# ST_LINK_V2-1.net
KiCad netlist of a schematic drawn in Altium Designer
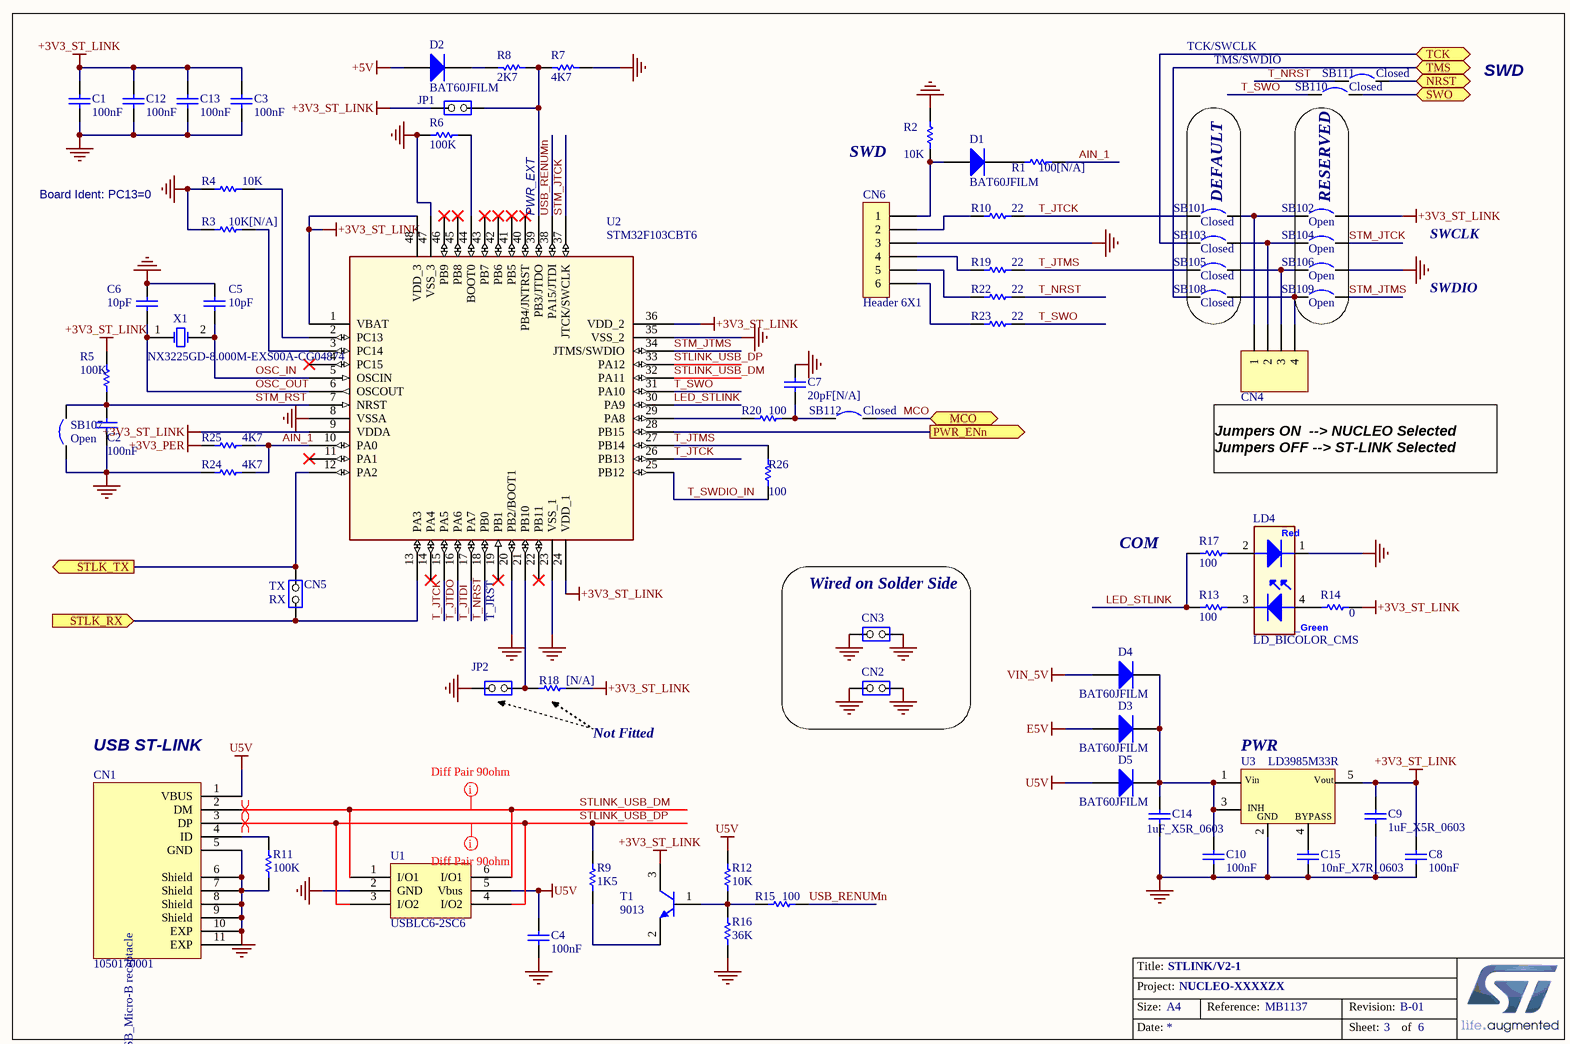
[diagram p0: ST_LINK_V2-1.SCHDOC]

(export (version "E")
  (design (tool "Eeschema 10.0.6"))
  (components
    (comp (ref "C1")
      (value "100nF")
      (footprint "0603C")
      (description "Capacitor 0402 / 0603 / 0805")
      (libsource (lib "MCD_TOOLS") (part "Capacitor_ST"))
    )
    (comp (ref "C2")
      (value "100nF")
      (footprint "0603C")
      (description "Capacitor 0402 / 0603 / 0805")
      (libsource (lib "MCD_TOOLS") (part "Capacitor_ST"))
    )
    (comp (ref "C3")
      (value "100nF")
      (footprint "0603C")
      (description "Capacitor 0402 / 0603 / 0805")
      (libsource (lib "MCD_TOOLS") (part "Capacitor_ST"))
    )
    (comp (ref "C4")
      (value "100nF")
      (footprint "0603C")
      (description "Capacitor 0402 / 0603 / 0805")
      (libsource (lib "MCD_TOOLS") (part "Capacitor_ST"))
    )
    (comp (ref "C5")
      (value "10pF")
      (footprint "0603C")
      (description "Capacitor 0402 / 0603 / 0805")
      (libsource (lib "MCD_TOOLS") (part "Capacitor_ST"))
    )
    (comp (ref "C6")
      (value "10pF")
      (footprint "0603C")
      (description "Capacitor 0402 / 0603 / 0805")
      (libsource (lib "MCD_TOOLS") (part "Capacitor_ST"))
    )
    (comp (ref "C7")
      (value "20pF[N/A]")
      (footprint "0603C")
      (description "Capacitor 0402 / 0603 / 0805")
      (libsource (lib "MCD_TOOLS") (part "Capacitor_ST"))
    )
    (comp (ref "C8")
      (value "100nF")
      (footprint "0603C")
      (description "Capacitor 0402 / 0603 / 0805")
      (libsource (lib "MCD_TOOLS") (part "Capacitor_ST"))
    )
    (comp (ref "C9")
      (value "1uF_X5R_0603")
      (footprint "0603C")
      (description "0603  X5R 1µF")
      (fields (field (name "TOLERANCE") "10%"))
      (libsource (lib "MB963_1") (part "CAP SMD 0603  X5R 1µF 25V 10%"))
    )
    (comp (ref "C10")
      (value "100nF")
      (footprint "0603C")
      (description "Capacitor 0402 / 0603 / 0805")
      (libsource (lib "MCD_TOOLS") (part "Capacitor_ST"))
    )
    (comp (ref "C12")
      (value "100nF")
      (footprint "0603C")
      (description "Capacitor 0402 / 0603 / 0805")
      (libsource (lib "MCD_TOOLS") (part "Capacitor_ST"))
    )
    (comp (ref "C13")
      (value "100nF")
      (footprint "0603C")
      (description "Capacitor 0402 / 0603 / 0805")
      (libsource (lib "MCD_TOOLS") (part "Capacitor_ST"))
    )
    (comp (ref "C14")
      (value "1uF_X5R_0603")
      (footprint "0603C")
      (description "0603  X5R 1µF")
      (fields (field (name "TOLERANCE") "10%"))
      (libsource (lib "MB963_1") (part "CAP SMD 0603  X5R 1µF 25V 10%"))
    )
    (comp (ref "C15")
      (value "10nF_X7R_0603")
      (footprint "0603C")
      (description "0603  X7R 10NF")
      (fields (field (name "TOLERANCE") "10%"))
      (libsource (lib "MB963_1") (part "CAP SMD 0603  X7R 10000PF 50V 10%"))
    )
    (comp (ref "CN1")
      (value "1050170001")
      (footprint "Molex_1050170001")
      (libsource (lib "Smartphone_accessory") (part "1050170001"))
    )
    (comp (ref "CN2") (value "~") (footprint "HDR_1x2_2R54_V_M") (libsource (lib "*") (part "JP2")))
    (comp (ref "CN3") (value "~") (footprint "HDR_1x2_2R54_V_M") (libsource (lib "*") (part "JP2")))
    (comp (ref "CN4")
      (value "Header 4")
      (footprint "HDR_1x4_2R54_V_M")
      (description "Header, 4-Pin, Single row")
      (fields (field (name "PUBLISHER") "Altium Limited"))
      (libsource (lib "Nucleo_64") (part "Header 4"))
    )
    (comp (ref "CN5") (value "~") (footprint "HDR_1x2_2R54_V_M_S") (libsource (lib "MCD_TOOLS") (part "JP2")))
    (comp (ref "CN6")
      (value "Header 6X1")
      (footprint "HDR_1x6_2R54_V_M")
      (description "Header, 6-Pin, Single row")
      (fields (field (name "PUBLISHER") "Altium Limited"))
      (libsource (lib "Nucleo_64") (part "Header 6X1"))
    )
    (comp (ref "D1")
      (value "BAT60JFILM")
      (footprint "SOD-323")
      (libsource (lib "MB1137") (part "BAT60JFILM"))
    )
    (comp (ref "D2")
      (value "BAT60JFILM")
      (footprint "SOD-323")
      (description "Default Diode")
      (fields (field (name "PUBLISHER") "Altium Limited"))
      (libsource (lib "MB1144_1") (part "Diode"))
    )
    (comp (ref "D3")
      (value "BAT60JFILM")
      (footprint "SOD-323")
      (libsource (lib "MB1137") (part "BAT60JFILM"))
    )
    (comp (ref "D4")
      (value "BAT60JFILM")
      (footprint "SOD-323")
      (libsource (lib "MB1137") (part "BAT60JFILM"))
    )
    (comp (ref "D5")
      (value "BAT60JFILM")
      (footprint "SOD-323")
      (libsource (lib "MB1137") (part "BAT60JFILM"))
    )
    (comp (ref "JP1") (value "~") (footprint "HDR_1x2_2R54_V_M_S") (libsource (lib "*") (part "JP2")))
    (comp (ref "JP2") (value "~") (footprint "HDR_1x2_2R54_V_M_S") (libsource (lib "*") (part "JP2")))
    (comp (ref "LD4")
      (value "LD_BICOLOR_CMS")
      (footprint "HSMF-A201")
      (description "Bicolor Led")
      (libsource (lib "MB1137") (part "LD_BICOLOR_CMS"))
    )
    (comp (ref "R1")
      (value "100[N/A]")
      (footprint "0603R")
      (description "Resistor 0402 or 0603 or 0805")
      (libsource (lib "") (part "Res1_1"))
    )
    (comp (ref "R2")
      (value "10K")
      (footprint "0603R")
      (description "Resistor 0402 or 0603 or 0805")
      (libsource (lib "") (part "Res1_1"))
    )
    (comp (ref "R3")
      (value "10K[N/A]")
      (footprint "0603R")
      (description "Resistor 0402 or 0603 or 0805")
      (libsource (lib "") (part "Res1_1"))
    )
    (comp (ref "R4")
      (value "10K")
      (footprint "0603R")
      (description "Resistor 0402 or 0603 or 0805")
      (libsource (lib "") (part "Res1_1"))
    )
    (comp (ref "R5")
      (value "100K")
      (footprint "0603R")
      (description "Resistor 0402 or 0603 or 0805")
      (libsource (lib "") (part "Res1_1"))
    )
    (comp (ref "R6")
      (value "100K")
      (footprint "0603R")
      (description "Resistor 0402 or 0603 or 0805")
      (libsource (lib "") (part "Res1_1"))
    )
    (comp (ref "R7")
      (value "4K7")
      (footprint "0603R")
      (description "Resistor")
      (fields (field (name "PUBLISHER") "Altium Limited"))
      (libsource (lib "") (part "Res1_2"))
    )
    (comp (ref "R8")
      (value "2K7")
      (footprint "0603R")
      (description "Resistor")
      (fields (field (name "PUBLISHER") "Altium Limited"))
      (libsource (lib "") (part "Res1_2"))
    )
    (comp (ref "R9")
      (value "1K5")
      (footprint "0603R")
      (description "Resistor 0402 or 0603 or 0805")
      (libsource (lib "") (part "Res1_1"))
    )
    (comp (ref "R10")
      (value "22")
      (footprint "0603R")
      (description "Resistor 0402 or 0603 or 0805")
      (libsource (lib "") (part "Res1_1"))
    )
    (comp (ref "R11")
      (value "100K")
      (footprint "0603R")
      (description "Resistor 0402 or 0603 or 0805")
      (libsource (lib "") (part "Res1_1"))
    )
    (comp (ref "R12")
      (value "10K")
      (footprint "0603R")
      (description "Resistor")
      (fields (field (name "PUBLISHER") "Altium Limited"))
      (libsource (lib "Miscellaneous Devices") (part "Res1"))
    )
    (comp (ref "R13")
      (value "100")
      (footprint "0603R")
      (description "Resistor 0402 or 0603 or 0805")
      (libsource (lib "") (part "Res1_1"))
    )
    (comp (ref "R14")
      (value "0")
      (footprint "0603R")
      (description "Resistor 0402 or 0603 or 0805")
      (libsource (lib "") (part "Res1_1"))
    )
    (comp (ref "R15")
      (value "100")
      (footprint "0603R")
      (description "Resistor 0402 or 0603 or 0805")
      (libsource (lib "") (part "Res1_1"))
    )
    (comp (ref "R16")
      (value "36K")
      (footprint "0603R")
      (description "Resistor")
      (fields (field (name "PUBLISHER") "Altium Limited"))
      (libsource (lib "Miscellaneous Devices") (part "Res1"))
    )
    (comp (ref "R17")
      (value "100")
      (footprint "0603R")
      (description "Resistor 0402 or 0603 or 0805")
      (libsource (lib "") (part "Res1_1"))
    )
    (comp (ref "R18")
      (value "[N/A]")
      (footprint "0603R")
      (description "Resistor")
      (fields (field (name "PUBLISHER") "Altium Limited"))
      (libsource (lib "Miscellaneous Devices") (part "Res1"))
    )
    (comp (ref "R19")
      (value "22")
      (footprint "0603R")
      (description "Resistor 0402 or 0603 or 0805")
      (libsource (lib "") (part "Res1_1"))
    )
    (comp (ref "R20")
      (value "100")
      (footprint "0603R")
      (description "Resistor 0402 or 0603 or 0805")
      (libsource (lib "") (part "Res1_1"))
    )
    (comp (ref "R22")
      (value "22")
      (footprint "0603R")
      (description "Resistor 0402 or 0603 or 0805")
      (libsource (lib "") (part "Res1_1"))
    )
    (comp (ref "R23")
      (value "22")
      (footprint "0603R")
      (description "Resistor 0402 or 0603 or 0805")
      (libsource (lib "") (part "Res1_1"))
    )
    (comp (ref "R24")
      (value "4K7")
      (footprint "0603R")
      (description "Resistor 0402 or 0603 or 0805")
      (libsource (lib "") (part "Res1_1"))
    )
    (comp (ref "R25")
      (value "4K7")
      (footprint "0603R")
      (description "Resistor 0402 or 0603 or 0805")
      (libsource (lib "") (part "Res1_1"))
    )
    (comp (ref "R26")
      (value "100")
      (footprint "0603R")
      (description "Resistor 0402 or 0603 or 0805")
      (libsource (lib "") (part "Res1_1"))
    )
    (comp (ref "SB101")
      (value "Closed")
      (footprint "SB_0603")
      (description "Circuit Breaker")
      (fields (field (name "PUBLISHER") "Altium Limited"))
      (libsource (lib "MB1167") (part "Circuit Breaker_close"))
    )
    (comp (ref "SB102")
      (value "Open")
      (footprint "SB_0603")
      (description "Circuit Breaker")
      (fields (field (name "PUBLISHER") "Altium Limited"))
      (libsource (lib "MB1167") (part "Circuit Breaker"))
    )
    (comp (ref "SB103")
      (value "Closed")
      (footprint "SB_0603")
      (description "Circuit Breaker")
      (fields (field (name "PUBLISHER") "Altium Limited"))
      (libsource (lib "MB1167") (part "Circuit Breaker_close"))
    )
    (comp (ref "SB104")
      (value "Open")
      (footprint "SB_0603")
      (description "Circuit Breaker")
      (fields (field (name "PUBLISHER") "Altium Limited"))
      (libsource (lib "MB1167") (part "Circuit Breaker"))
    )
    (comp (ref "SB105")
      (value "Closed")
      (footprint "SB_0603")
      (description "Circuit Breaker")
      (fields (field (name "PUBLISHER") "Altium Limited"))
      (libsource (lib "MB1167") (part "Circuit Breaker_close"))
    )
    (comp (ref "SB106")
      (value "Open")
      (footprint "SB_0603")
      (description "Circuit Breaker")
      (fields (field (name "PUBLISHER") "Altium Limited"))
      (libsource (lib "MB1167") (part "Circuit Breaker"))
    )
    (comp (ref "SB107")
      (value "Open")
      (footprint "SB_0603")
      (description "Circuit Breaker")
      (fields (field (name "PUBLISHER") "Altium Limited"))
      (libsource (lib "MB1167") (part "Circuit Breaker"))
    )
    (comp (ref "SB108")
      (value "Closed")
      (footprint "SB_0603")
      (description "Circuit Breaker")
      (fields (field (name "PUBLISHER") "Altium Limited"))
      (libsource (lib "MB1167") (part "Circuit Breaker_close"))
    )
    (comp (ref "SB109")
      (value "Open")
      (footprint "SB_0603")
      (description "Circuit Breaker")
      (fields (field (name "PUBLISHER") "Altium Limited"))
      (libsource (lib "MB1167") (part "Circuit Breaker"))
    )
    (comp (ref "SB110")
      (value "Closed")
      (footprint "SB_0603")
      (description "Circuit Breaker")
      (fields (field (name "PUBLISHER") "Altium Limited"))
      (libsource (lib "MB1167") (part "Circuit Breaker_close"))
    )
    (comp (ref "SB111")
      (value "Closed")
      (footprint "SB_0603")
      (description "Circuit Breaker")
      (fields (field (name "PUBLISHER") "Altium Limited"))
      (libsource (lib "MB1167") (part "Circuit Breaker_close"))
    )
    (comp (ref "SB112")
      (value "Closed")
      (footprint "SB_0603")
      (description "Circuit Breaker")
      (fields (field (name "PUBLISHER") "Altium Limited"))
      (libsource (lib "MB1167") (part "Circuit Breaker_close"))
    )
    (comp (ref "T1")
      (value "9013")
      (footprint "SOT-23")
      (description "NPN Bipolar Transistor")
      (fields (field (name "PUBLISHER") "Altium Limited"))
      (libsource (lib "MB1167") (part "NPN"))
    )
    (comp (ref "U1")
      (value "USBLC6-2SC6")
      (footprint "SOT23-6L")
      (libsource (lib "MB1137") (part "USBLC6-2SC6"))
    )
    (comp (ref "U2")
      (value "STM32F103CBT6")
      (footprint "LQFP48_0R5_7x7")
      (description "Medium-density performance line ARM-based 32-bit MCU with 64KB Flash")
      (libsource (lib "Nucleo_64") (part "STM32F103CBT6"))
    )
    (comp (ref "U3")
      (value "LD3985M33R")
      (footprint "SOT-23-5L")
      (description "Ultra low drop-low noise BiCMOS voltage, regulators low ESR capacitors compatible")
      (libsource (lib "MCD_TOOLS") (part "LD3985M33R"))
    )
    (comp (ref "X1")
      (value "NX3225GD-8.000M-EXS00A-CG04874")
      (footprint "OSC_2SM_3R2x2R5")
      (description "Crystal Oscillator")
      (fields (field (name "PUBLISHER") "Altium Limited"))
      (libsource (lib "MB963_1") (part "XTAL"))
    )
  )
  (nets
    (net (code "1") (name "+3V3_PER") (class "Default")
      (node (ref "R25") (pin "1") (pinfunction "1_1") (pintype "passive"))
    )
    (net (code "2") (name "+3V3_ST_LINK") (class "Default")
      (node (ref "C1") (pin "2") (pinfunction "2_2") (pintype "passive"))
      (node (ref "C12") (pin "2") (pinfunction "2_2") (pintype "passive"))
      (node (ref "C13") (pin "2") (pinfunction "2_2") (pintype "passive"))
      (node (ref "C3") (pin "2") (pinfunction "2_2") (pintype "passive"))
      (node (ref "C8") (pin "2") (pinfunction "2_2") (pintype "passive"))
      (node (ref "C9") (pin "1") (pinfunction "1_1") (pintype "passive"))
      (node (ref "JP1") (pin "1") (pinfunction "COMMON_1") (pintype "passive"))
      (node (ref "R14") (pin "2") (pinfunction "2_2") (pintype "passive"))
      (node (ref "R18") (pin "1") (pinfunction "1_1") (pintype "passive"))
      (node (ref "R5") (pin "2") (pinfunction "2_2") (pintype "passive"))
      (node (ref "SB102") (pin "2") (pinfunction "2_2") (pintype "passive"))
      (node (ref "T1") (pin "3") (pinfunction "C_3") (pintype "passive"))
      (node (ref "U2") (pin "1") (pinfunction "VBAT_1") (pintype "power_in"))
      (node (ref "U2") (pin "24") (pinfunction "VDD_1_24") (pintype "power_in"))
      (node (ref "U2") (pin "36") (pinfunction "VDD_2_36") (pintype "power_in"))
      (node (ref "U2") (pin "48") (pinfunction "VDD_3_48") (pintype "power_in"))
      (node (ref "U2") (pin "9") (pinfunction "VDDA_9") (pintype "power_in"))
      (node (ref "U3") (pin "5") (pinfunction "Vout_5") (pintype "passive"))
    )
    (net (code "3") (name "+5V") (class "Default")
      (node (ref "D2") (pin "1") (pinfunction "A_1") (pintype "passive"))
    )
    (net (code "4") (name "/AIN_1") (class "Default")
      (node (ref "R1") (pin "2") (pinfunction "2_2") (pintype "passive"))
      (node (ref "R24") (pin "2") (pinfunction "2_2") (pintype "passive"))
      (node (ref "R25") (pin "2") (pinfunction "2_2") (pintype "passive"))
      (node (ref "U2") (pin "10") (pinfunction "PA0_10") (pintype "bidirectional"))
    )
    (net (code "5") (name "/LED_STLINK") (class "Default")
      (node (ref "R13") (pin "1") (pinfunction "1_1") (pintype "passive"))
      (node (ref "R17") (pin "1") (pinfunction "1_1") (pintype "passive"))
      (node (ref "U2") (pin "30") (pinfunction "PA9_30") (pintype "bidirectional"))
    )
    (net (code "6") (name "/MCO") (class "Default")
      (node (ref "SB112") (pin "2") (pinfunction "2_2") (pintype "passive"))
    )
    (net (code "7") (name "/NRST") (class "Default")
      (node (ref "SB111") (pin "2") (pinfunction "2_2") (pintype "passive"))
    )
    (net (code "8") (name "/OSC_IN") (class "Default")
      (node (ref "C5") (pin "1") (pinfunction "1_1") (pintype "passive"))
      (node (ref "U2") (pin "5") (pinfunction "OSCIN_5") (pintype "input"))
      (node (ref "X1") (pin "2") (pinfunction "OSC2_2") (pintype "passive"))
    )
    (net (code "9") (name "/OSC_OUT") (class "Default")
      (node (ref "C6") (pin "1") (pinfunction "1_1") (pintype "passive"))
      (node (ref "U2") (pin "6") (pinfunction "OSCOUT_6") (pintype "output"))
      (node (ref "X1") (pin "1") (pinfunction "OSC1_1") (pintype "passive"))
    )
    (net (code "10") (name "/PWR_ENn") (class "Default")
      (node (ref "U2") (pin "28") (pinfunction "PB15_28") (pintype "bidirectional"))
    )
    (net (code "11") (name "/STLINK_USB_DM") (class "Default")
      (node (ref "CN1") (pin "2") (pinfunction "DM_2") (pintype "passive"))
      (node (ref "U1") (pin "1") (pinfunction "I/O1_1") (pintype "passive"))
      (node (ref "U1") (pin "6") (pinfunction "I/O1_6") (pintype "passive"))
      (node (ref "U2") (pin "32") (pinfunction "PA11_32") (pintype "bidirectional"))
    )
    (net (code "12") (name "/STLINK_USB_DP") (class "Default")
      (node (ref "CN1") (pin "3") (pinfunction "DP_3") (pintype "passive"))
      (node (ref "R9") (pin "1") (pinfunction "1_1") (pintype "passive"))
      (node (ref "U1") (pin "3") (pinfunction "I/O2_3") (pintype "passive"))
      (node (ref "U1") (pin "4") (pinfunction "I/O2_4") (pintype "passive"))
      (node (ref "U2") (pin "33") (pinfunction "PA12_33") (pintype "bidirectional"))
    )
    (net (code "13") (name "/STLK_RX") (class "Default")
      (node (ref "CN5") (pin "1") (pinfunction "COMMON_1") (pintype "passive"))
      (node (ref "U2") (pin "13") (pinfunction "PA3_13") (pintype "bidirectional"))
    )
    (net (code "14") (name "/STLK_TX") (class "Default")
      (node (ref "CN5") (pin "2") (pinfunction "NO_2") (pintype "passive"))
      (node (ref "U2") (pin "12") (pinfunction "PA2_12") (pintype "bidirectional"))
    )
    (net (code "15") (name "/STM_JTCK") (class "Default")
      (node (ref "SB104") (pin "2") (pinfunction "2_2") (pintype "passive"))
      (node (ref "U2") (pin "37") (pinfunction "JTCK/SWCLK_37") (pintype "bidirectional"))
    )
    (net (code "16") (name "/STM_JTMS") (class "Default")
      (node (ref "SB109") (pin "2") (pinfunction "2_2") (pintype "passive"))
      (node (ref "U2") (pin "34") (pinfunction "JTMS/SWDIO_34") (pintype "bidirectional"))
    )
    (net (code "17") (name "/STM_RST") (class "Default")
      (node (ref "C2") (pin "2") (pinfunction "2_2") (pintype "passive"))
      (node (ref "R5") (pin "1") (pinfunction "1_1") (pintype "passive"))
      (node (ref "SB107") (pin "2") (pinfunction "2_2") (pintype "passive"))
      (node (ref "U2") (pin "7") (pinfunction "NRST_7") (pintype "input"))
    )
    (net (code "18") (name "/SWO") (class "Default")
      (node (ref "SB110") (pin "2") (pinfunction "2_2") (pintype "passive"))
    )
    (net (code "19") (name "/TCK") (class "Default")
      (node (ref "SB103") (pin "1") (pinfunction "1_1") (pintype "passive"))
    )
    (net (code "20") (name "/TMS") (class "Default")
      (node (ref "SB108") (pin "1") (pinfunction "1_1") (pintype "passive"))
    )
    (net (code "21") (name "/T_JTCK") (class "Default")
      (node (ref "R10") (pin "2") (pinfunction "2_2") (pintype "passive"))
      (node (ref "SB101") (pin "1") (pinfunction "1_1") (pintype "passive"))
      (node (ref "U2") (pin "15") (pinfunction "PA5_15") (pintype "bidirectional"))
      (node (ref "U2") (pin "26") (pinfunction "PB13_26") (pintype "bidirectional"))
    )
    (net (code "22") (name "/T_JTDI") (class "Default")
      (node (ref "U2") (pin "17") (pinfunction "PA7_17") (pintype "bidirectional"))
    )
    (net (code "23") (name "/T_JTDO") (class "Default")
      (node (ref "U2") (pin "16") (pinfunction "PA6_16") (pintype "bidirectional"))
    )
    (net (code "24") (name "/T_JTMS") (class "Default")
      (node (ref "R19") (pin "2") (pinfunction "2_2") (pintype "passive"))
      (node (ref "R26") (pin "2") (pinfunction "2_2") (pintype "passive"))
      (node (ref "SB105") (pin "1") (pinfunction "1_1") (pintype "passive"))
      (node (ref "U2") (pin "27") (pinfunction "PB14_27") (pintype "bidirectional"))
    )
    (net (code "25") (name "/T_NRST") (class "Default")
      (node (ref "R22") (pin "2") (pinfunction "2_2") (pintype "passive"))
      (node (ref "SB111") (pin "1") (pinfunction "1_1") (pintype "passive"))
      (node (ref "U2") (pin "18") (pinfunction "PB0_18") (pintype "bidirectional"))
    )
    (net (code "26") (name "/T_SWDIO_IN") (class "Default")
      (node (ref "R26") (pin "1") (pinfunction "1_1") (pintype "passive"))
      (node (ref "U2") (pin "25") (pinfunction "PB12_25") (pintype "bidirectional"))
    )
    (net (code "27") (name "/T_SWO") (class "Default")
      (node (ref "R23") (pin "2") (pinfunction "2_2") (pintype "passive"))
      (node (ref "SB110") (pin "1") (pinfunction "1_1") (pintype "passive"))
      (node (ref "U2") (pin "31") (pinfunction "PA10_31") (pintype "bidirectional"))
    )
    (net (code "28") (name "/USB_RENUMn") (class "Default")
      (node (ref "R15") (pin "2") (pinfunction "2_2") (pintype "passive"))
      (node (ref "U2") (pin "38") (pinfunction "PA15/JTDI_38") (pintype "bidirectional"))
    )
    (net (code "29") (name "E5V") (class "Default")
      (node (ref "D3") (pin "1") (pinfunction "A_1") (pintype "passive"))
    )
    (net (code "30") (name "GND") (class "Default")
      (node (ref "C1") (pin "1") (pinfunction "1_1") (pintype "passive"))
      (node (ref "C10") (pin "1") (pinfunction "1_1") (pintype "passive"))
      (node (ref "C12") (pin "1") (pinfunction "1_1") (pintype "passive"))
      (node (ref "C13") (pin "1") (pinfunction "1_1") (pintype "passive"))
      (node (ref "C14") (pin "1") (pinfunction "1_1") (pintype "passive"))
      (node (ref "C15") (pin "1") (pinfunction "1_1") (pintype "passive"))
      (node (ref "C2") (pin "1") (pinfunction "1_1") (pintype "passive"))
      (node (ref "C3") (pin "1") (pinfunction "1_1") (pintype "passive"))
      (node (ref "C4") (pin "1") (pinfunction "1_1") (pintype "passive"))
      (node (ref "C5") (pin "2") (pinfunction "2_2") (pintype "passive"))
      (node (ref "C6") (pin "2") (pinfunction "2_2") (pintype "passive"))
      (node (ref "C7") (pin "2") (pinfunction "2_2") (pintype "passive"))
      (node (ref "C8") (pin "1") (pinfunction "1_1") (pintype "passive"))
      (node (ref "C9") (pin "2") (pinfunction "2_2") (pintype "passive"))
      (node (ref "CN1") (pin "10") (pinfunction "EXP_10") (pintype "passive"))
      (node (ref "CN1") (pin "5") (pinfunction "GND_5") (pintype "passive"))
      (node (ref "CN1") (pin "6") (pinfunction "Shield_6") (pintype "passive"))
      (node (ref "CN1") (pin "7") (pinfunction "Shield_7") (pintype "passive"))
      (node (ref "CN1") (pin "8") (pinfunction "Shield_8") (pintype "passive"))
      (node (ref "CN1") (pin "9") (pinfunction "Shield_9") (pintype "passive"))
      (node (ref "CN2") (pin "1") (pinfunction "COMMON_1") (pintype "passive"))
      (node (ref "CN2") (pin "2") (pinfunction "NO_2") (pintype "passive"))
      (node (ref "CN3") (pin "1") (pinfunction "COMMON_1") (pintype "passive"))
      (node (ref "CN3") (pin "2") (pinfunction "NO_2") (pintype "passive"))
      (node (ref "CN6") (pin "3") (pinfunction "3_3") (pintype "passive"))
      (node (ref "JP2") (pin "1") (pinfunction "COMMON_1") (pintype "passive"))
      (node (ref "LD4") (pin "1") (pinfunction "1_1") (pintype "passive"))
      (node (ref "R11") (pin "2") (pinfunction "2_2") (pintype "passive"))
      (node (ref "R16") (pin "1") (pinfunction "1_1") (pintype "passive"))
      (node (ref "R2") (pin "2") (pinfunction "2_2") (pintype "passive"))
      (node (ref "R24") (pin "1") (pinfunction "1_1") (pintype "passive"))
      (node (ref "R3") (pin "1") (pinfunction "1_1") (pintype "passive"))
      (node (ref "R4") (pin "1") (pinfunction "1_1") (pintype "passive"))
      (node (ref "R6") (pin "1") (pinfunction "1_1") (pintype "passive"))
      (node (ref "R7") (pin "2") (pinfunction "2_2") (pintype "passive"))
      (node (ref "SB106") (pin "2") (pinfunction "2_2") (pintype "passive"))
      (node (ref "SB107") (pin "1") (pinfunction "1_1") (pintype "passive"))
      (node (ref "U1") (pin "2") (pinfunction "GND_2") (pintype "passive"))
      (node (ref "U2") (pin "20") (pinfunction "PB2/BOOT1_20") (pintype "bidirectional"))
      (node (ref "U2") (pin "23") (pinfunction "VSS_1_23") (pintype "power_in"))
      (node (ref "U2") (pin "35") (pinfunction "VSS_2_35") (pintype "power_in"))
      (node (ref "U2") (pin "47") (pinfunction "VSS_3_47") (pintype "power_in"))
      (node (ref "U2") (pin "8") (pinfunction "VSSA_8") (pintype "power_in"))
      (node (ref "U3") (pin "2") (pinfunction "GND_2") (pintype "passive"))
    )
    (net (code "31") (name "Net-(C7-Pad1)") (class "Default")
      (node (ref "C7") (pin "1") (pinfunction "1_1") (pintype "passive"))
      (node (ref "R20") (pin "2") (pinfunction "2_2") (pintype "passive"))
      (node (ref "SB112") (pin "1") (pinfunction "1_1") (pintype "passive"))
    )
    (net (code "32") (name "Net-(CN1-ID)") (class "Default")
      (node (ref "CN1") (pin "4") (pinfunction "ID_4") (pintype "passive"))
      (node (ref "R11") (pin "1") (pinfunction "1_1") (pintype "passive"))
    )
    (net (code "33") (name "Net-(CN4-Pad1)") (class "Default")
      (node (ref "CN4") (pin "1") (pinfunction "1_1") (pintype "passive"))
      (node (ref "SB101") (pin "2") (pinfunction "2_2") (pintype "passive"))
      (node (ref "SB102") (pin "1") (pinfunction "1_1") (pintype "passive"))
    )
    (net (code "34") (name "Net-(CN4-Pad2)") (class "Default")
      (node (ref "CN4") (pin "2") (pinfunction "2_2") (pintype "passive"))
      (node (ref "SB103") (pin "2") (pinfunction "2_2") (pintype "passive"))
      (node (ref "SB104") (pin "1") (pinfunction "1_1") (pintype "passive"))
    )
    (net (code "35") (name "Net-(CN4-Pad3)") (class "Default")
      (node (ref "CN4") (pin "3") (pinfunction "3_3") (pintype "passive"))
      (node (ref "SB105") (pin "2") (pinfunction "2_2") (pintype "passive"))
      (node (ref "SB106") (pin "1") (pinfunction "1_1") (pintype "passive"))
    )
    (net (code "36") (name "Net-(CN4-Pad4)") (class "Default")
      (node (ref "CN4") (pin "4") (pinfunction "4_4") (pintype "passive"))
      (node (ref "SB108") (pin "2") (pinfunction "2_2") (pintype "passive"))
      (node (ref "SB109") (pin "1") (pinfunction "1_1") (pintype "passive"))
    )
    (net (code "37") (name "Net-(CN6-Pad2)") (class "Default")
      (node (ref "CN6") (pin "2") (pinfunction "2_2") (pintype "passive"))
      (node (ref "R10") (pin "1") (pinfunction "1_1") (pintype "passive"))
    )
    (net (code "38") (name "Net-(CN6-Pad4)") (class "Default")
      (node (ref "CN6") (pin "4") (pinfunction "4_4") (pintype "passive"))
      (node (ref "R19") (pin "1") (pinfunction "1_1") (pintype "passive"))
    )
    (net (code "39") (name "Net-(CN6-Pad5)") (class "Default")
      (node (ref "CN6") (pin "5") (pinfunction "5_5") (pintype "passive"))
      (node (ref "R22") (pin "1") (pinfunction "1_1") (pintype "passive"))
    )
    (net (code "40") (name "Net-(CN6-Pad6)") (class "Default")
      (node (ref "CN6") (pin "6") (pinfunction "6_6") (pintype "passive"))
      (node (ref "R23") (pin "1") (pinfunction "1_1") (pintype "passive"))
    )
    (net (code "41") (name "Net-(D1-A)") (class "Default")
      (node (ref "CN6") (pin "1") (pinfunction "1_1") (pintype "passive"))
      (node (ref "D1") (pin "1") (pinfunction "A_1") (pintype "passive"))
      (node (ref "R2") (pin "1") (pinfunction "1_1") (pintype "passive"))
    )
    (net (code "42") (name "Net-(D1-K)") (class "Default")
      (node (ref "D1") (pin "2") (pinfunction "K_2") (pintype "passive"))
      (node (ref "R1") (pin "1") (pinfunction "1_1") (pintype "passive"))
    )
    (net (code "43") (name "Net-(D2-K)") (class "Default")
      (node (ref "D2") (pin "2") (pinfunction "K_2") (pintype "passive"))
      (node (ref "R8") (pin "1") (pinfunction "1_1") (pintype "passive"))
    )
    (net (code "44") (name "Net-(D3-K)") (class "Default")
      (node (ref "C10") (pin "2") (pinfunction "2_2") (pintype "passive"))
      (node (ref "C14") (pin "2") (pinfunction "2_2") (pintype "passive"))
      (node (ref "D3") (pin "2") (pinfunction "K_2") (pintype "passive"))
      (node (ref "D4") (pin "2") (pinfunction "K_2") (pintype "passive"))
      (node (ref "D5") (pin "2") (pinfunction "K_2") (pintype "passive"))
      (node (ref "U3") (pin "1") (pinfunction "Vin_1") (pintype "passive"))
      (node (ref "U3") (pin "3") (pinfunction "CE_3") (pintype "passive"))
    )
    (net (code "45") (name "Net-(JP1-NO)") (class "Default")
      (node (ref "JP1") (pin "2") (pinfunction "NO_2") (pintype "passive"))
      (node (ref "R7") (pin "1") (pinfunction "1_1") (pintype "passive"))
      (node (ref "R8") (pin "2") (pinfunction "2_2") (pintype "passive"))
      (node (ref "U2") (pin "39") (pinfunction "PB3/JTDO_39") (pintype "bidirectional"))
    )
    (net (code "46") (name "Net-(JP2-NO)") (class "Default")
      (node (ref "JP2") (pin "2") (pinfunction "NO_2") (pintype "passive"))
      (node (ref "R18") (pin "2") (pinfunction "2_2") (pintype "passive"))
      (node (ref "U2") (pin "21") (pinfunction "PB10_21") (pintype "bidirectional"))
    )
    (net (code "47") (name "Net-(LD4-Pad2)") (class "Default")
      (node (ref "LD4") (pin "2") (pinfunction "2_2") (pintype "passive"))
      (node (ref "R17") (pin "2") (pinfunction "2_2") (pintype "passive"))
    )
    (net (code "48") (name "Net-(LD4-Pad3)") (class "Default")
      (node (ref "LD4") (pin "3") (pinfunction "3_3") (pintype "passive"))
      (node (ref "R13") (pin "2") (pinfunction "2_2") (pintype "passive"))
    )
    (net (code "49") (name "Net-(LD4-Pad4)") (class "Default")
      (node (ref "LD4") (pin "4") (pinfunction "4_4") (pintype "passive"))
      (node (ref "R14") (pin "1") (pinfunction "1_1") (pintype "passive"))
    )
    (net (code "50") (name "Net-(T1-B)") (class "Default")
      (node (ref "R12") (pin "1") (pinfunction "1_1") (pintype "passive"))
      (node (ref "R15") (pin "1") (pinfunction "1_1") (pintype "passive"))
      (node (ref "R16") (pin "2") (pinfunction "2_2") (pintype "passive"))
      (node (ref "T1") (pin "1") (pinfunction "B_1") (pintype "passive"))
    )
    (net (code "51") (name "Net-(T1-E)") (class "Default")
      (node (ref "R9") (pin "2") (pinfunction "2_2") (pintype "passive"))
      (node (ref "T1") (pin "2") (pinfunction "E_2") (pintype "passive"))
    )
    (net (code "52") (name "Net-(U2-BOOT0)") (class "Default")
      (node (ref "R6") (pin "2") (pinfunction "2_2") (pintype "passive"))
      (node (ref "U2") (pin "44") (pinfunction "BOOT0_44") (pintype "bidirectional"))
    )
    (net (code "53") (name "Net-(U2-PA8)") (class "Default")
      (node (ref "R20") (pin "1") (pinfunction "1_1") (pintype "passive"))
      (node (ref "U2") (pin "29") (pinfunction "PA8_29") (pintype "bidirectional"))
    )
    (net (code "54") (name "Net-(U2-PC13)") (class "Default")
      (node (ref "R4") (pin "2") (pinfunction "2_2") (pintype "passive"))
      (node (ref "U2") (pin "2") (pinfunction "PC13_2") (pintype "bidirectional"))
    )
    (net (code "55") (name "Net-(U2-PC14)") (class "Default")
      (node (ref "R3") (pin "2") (pinfunction "2_2") (pintype "passive"))
      (node (ref "U2") (pin "3") (pinfunction "PC14_3") (pintype "bidirectional"))
    )
    (net (code "56") (name "Net-(U3-BYPASS)") (class "Default")
      (node (ref "C15") (pin "2") (pinfunction "2_2") (pintype "passive"))
      (node (ref "U3") (pin "4") (pinfunction "BYPASS_4") (pintype "passive"))
    )
    (net (code "57") (name "U5V") (class "Default")
      (node (ref "C4") (pin "2") (pinfunction "2_2") (pintype "passive"))
      (node (ref "CN1") (pin "1") (pinfunction "VBUS_1") (pintype "passive"))
      (node (ref "D5") (pin "1") (pinfunction "A_1") (pintype "passive"))
      (node (ref "R12") (pin "2") (pinfunction "2_2") (pintype "passive"))
      (node (ref "U1") (pin "5") (pinfunction "Vbus_5") (pintype "passive"))
    )
    (net (code "58") (name "VIN_5V") (class "Default")
      (node (ref "D4") (pin "1") (pinfunction "A_1") (pintype "passive"))
    )
    (net (code "59") (name "unconnected-(CN1-EXP-Pad11)") (class "Default")
      (node (ref "CN1") (pin "11") (pinfunction "EXP_11") (pintype "passive"))
    )
    (net (code "60") (name "unconnected-(U2-PA1-Pad11)") (class "Default")
      (node (ref "U2") (pin "11") (pinfunction "PA1_11") (pintype "bidirectional+no_connect"))
    )
    (net (code "61") (name "unconnected-(U2-PA4-Pad14)") (class "Default")
      (node (ref "U2") (pin "14") (pinfunction "PA4_14") (pintype "bidirectional+no_connect"))
    )
    (net (code "62") (name "unconnected-(U2-PB1-Pad19)") (class "Default")
      (node (ref "U2") (pin "19") (pinfunction "PB1_19") (pintype "input+no_connect"))
    )
    (net (code "63") (name "unconnected-(U2-PB4{slash}JNTRST-Pad40)") (class "Default")
      (node (ref "U2") (pin "40") (pinfunction "PB4/JNTRST_40") (pintype "bidirectional+no_connect"))
    )
    (net (code "64") (name "unconnected-(U2-PB5-Pad41)") (class "Default")
      (node (ref "U2") (pin "41") (pinfunction "PB5_41") (pintype "bidirectional+no_connect"))
    )
    (net (code "65") (name "unconnected-(U2-PB6-Pad42)") (class "Default")
      (node (ref "U2") (pin "42") (pinfunction "PB6_42") (pintype "bidirectional+no_connect"))
    )
    (net (code "66") (name "unconnected-(U2-PB7-Pad43)") (class "Default")
      (node (ref "U2") (pin "43") (pinfunction "PB7_43") (pintype "bidirectional+no_connect"))
    )
    (net (code "67") (name "unconnected-(U2-PB8-Pad45)") (class "Default")
      (node (ref "U2") (pin "45") (pinfunction "PB8_45") (pintype "bidirectional+no_connect"))
    )
    (net (code "68") (name "unconnected-(U2-PB9-Pad46)") (class "Default")
      (node (ref "U2") (pin "46") (pinfunction "PB9_46") (pintype "bidirectional+no_connect"))
    )
    (net (code "69") (name "unconnected-(U2-PB11-Pad22)") (class "Default")
      (node (ref "U2") (pin "22") (pinfunction "PB11_22") (pintype "bidirectional+no_connect"))
    )
    (net (code "70") (name "unconnected-(U2-PC15-Pad4)") (class "Default")
      (node (ref "U2") (pin "4") (pinfunction "PC15_4") (pintype "bidirectional+no_connect"))
    )
  )
)
